# BaseBoard.net
KiCad netlist of a schematic drawn in EasyEDA Pro
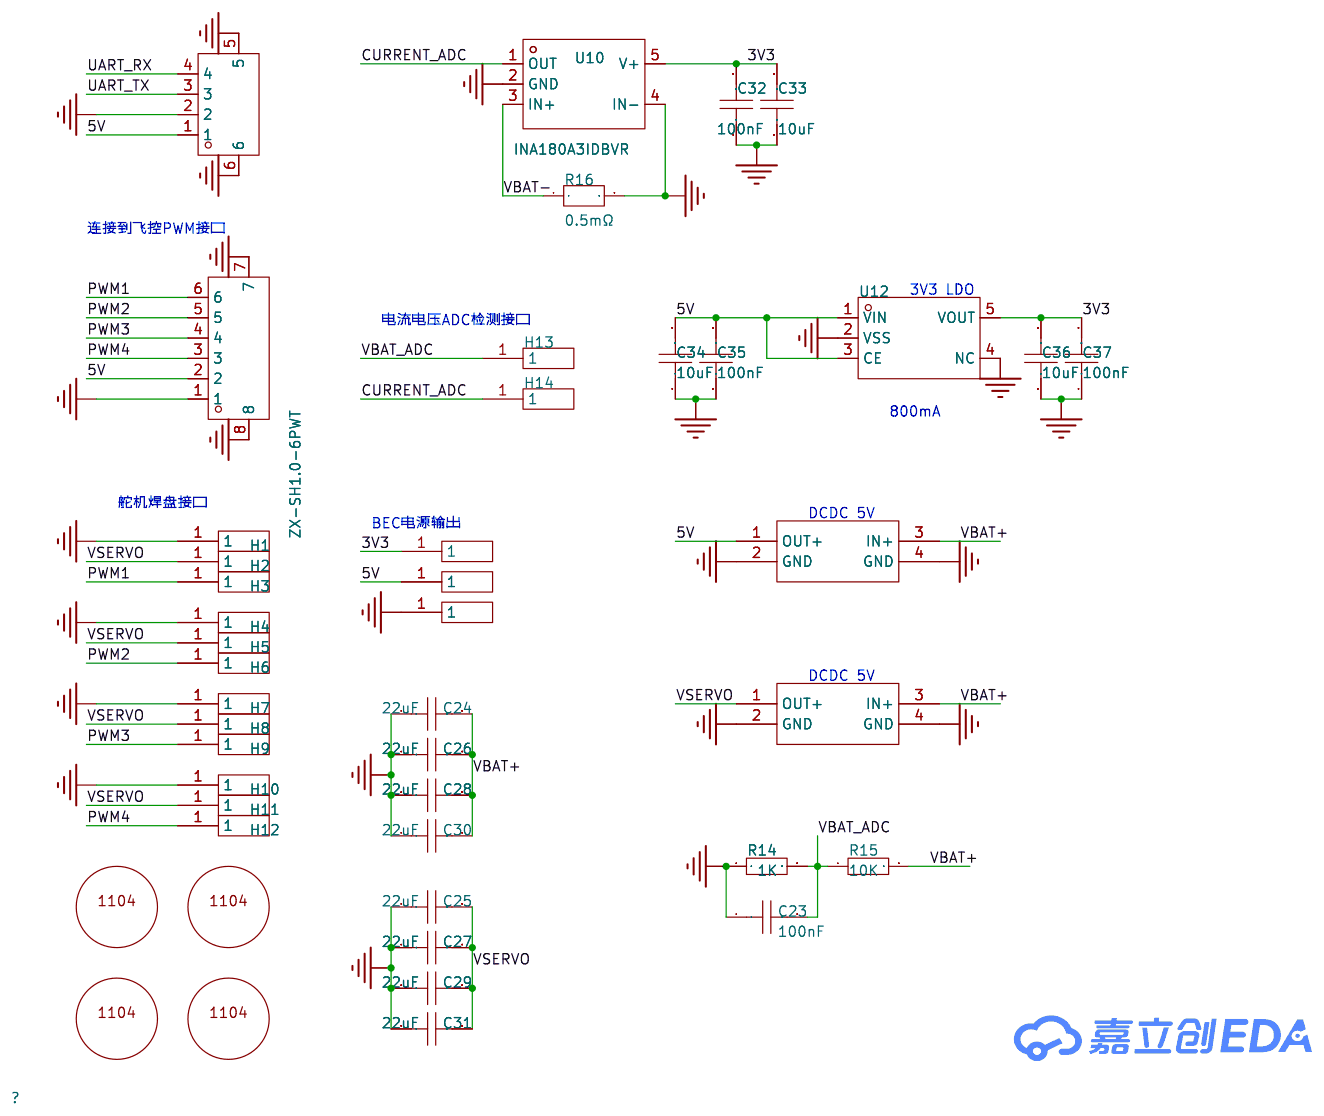
[diagram p0: schematic sheet]

(export (version "E")
  (design (tool "Eeschema 10.0.6"))
  (components
    (comp (ref "C23")
      (value "100nF")
      (footprint "easyedapro:C0805")
      (libsource (lib "easyedapro") (part "CapAcitance"))
    )
    (comp (ref "C24")
      (value "22uF")
      (footprint "easyedapro:C0805")
      (libsource (lib "easyedapro") (part "CapAcitance"))
    )
    (comp (ref "C25")
      (value "22uF")
      (footprint "easyedapro:C0805")
      (libsource (lib "easyedapro") (part "CapAcitance"))
    )
    (comp (ref "C26")
      (value "22uF")
      (footprint "easyedapro:C0805")
      (libsource (lib "easyedapro") (part "CapAcitance"))
    )
    (comp (ref "C27")
      (value "22uF")
      (footprint "easyedapro:C0805")
      (libsource (lib "easyedapro") (part "CapAcitance"))
    )
    (comp (ref "C28")
      (value "22uF")
      (footprint "easyedapro:C0805")
      (libsource (lib "easyedapro") (part "CapAcitance"))
    )
    (comp (ref "C29")
      (value "22uF")
      (footprint "easyedapro:C0805")
      (libsource (lib "easyedapro") (part "CapAcitance"))
    )
    (comp (ref "C30")
      (value "22uF")
      (footprint "easyedapro:C0805")
      (libsource (lib "easyedapro") (part "CapAcitance"))
    )
    (comp (ref "C31")
      (value "22uF")
      (footprint "easyedapro:C0805")
      (libsource (lib "easyedapro") (part "CapAcitance"))
    )
    (comp (ref "C32")
      (value "100nF")
      (footprint "easyedapro:C0805")
      (libsource (lib "easyedapro") (part "CapAcitance"))
    )
    (comp (ref "C33")
      (value "10uF")
      (footprint "easyedapro:C0805")
      (libsource (lib "easyedapro") (part "CapAcitance"))
    )
    (comp (ref "C34")
      (value "10uF")
      (footprint "easyedapro:C0805")
      (libsource (lib "easyedapro") (part "CapAcitance"))
    )
    (comp (ref "C35")
      (value "100nF")
      (footprint "easyedapro:C0805")
      (libsource (lib "easyedapro") (part "CapAcitance"))
    )
    (comp (ref "C36")
      (value "10uF")
      (footprint "easyedapro:C0805")
      (libsource (lib "easyedapro") (part "CapAcitance"))
    )
    (comp (ref "C37")
      (value "100nF")
      (footprint "easyedapro:C0805")
      (libsource (lib "easyedapro") (part "CapAcitance"))
    )
    (comp (ref "H1")
      (value "~")
      (footprint "easyedapro:飞控微型焊盘")
      (description "20250513 绘制接收机使用")
      (libsource (lib "easyedapro") (part "飞控微型焊盘"))
    )
    (comp (ref "H2")
      (value "~")
      (footprint "easyedapro:飞控微型焊盘")
      (description "20250513 绘制接收机使用")
      (libsource (lib "easyedapro") (part "飞控微型焊盘"))
    )
    (comp (ref "H3")
      (value "~")
      (footprint "easyedapro:飞控微型焊盘")
      (description "20250513 绘制接收机使用")
      (libsource (lib "easyedapro") (part "飞控微型焊盘"))
    )
    (comp (ref "H4")
      (value "~")
      (footprint "easyedapro:飞控微型焊盘")
      (description "20250513 绘制接收机使用")
      (libsource (lib "easyedapro") (part "飞控微型焊盘"))
    )
    (comp (ref "H5")
      (value "~")
      (footprint "easyedapro:飞控微型焊盘")
      (description "20250513 绘制接收机使用")
      (libsource (lib "easyedapro") (part "飞控微型焊盘"))
    )
    (comp (ref "H6")
      (value "~")
      (footprint "easyedapro:飞控微型焊盘")
      (description "20250513 绘制接收机使用")
      (libsource (lib "easyedapro") (part "飞控微型焊盘"))
    )
    (comp (ref "H7")
      (value "~")
      (footprint "easyedapro:飞控微型焊盘")
      (description "20250513 绘制接收机使用")
      (libsource (lib "easyedapro") (part "飞控微型焊盘"))
    )
    (comp (ref "H8")
      (value "~")
      (footprint "easyedapro:飞控微型焊盘")
      (description "20250513 绘制接收机使用")
      (libsource (lib "easyedapro") (part "飞控微型焊盘"))
    )
    (comp (ref "H9")
      (value "~")
      (footprint "easyedapro:飞控微型焊盘")
      (description "20250513 绘制接收机使用")
      (libsource (lib "easyedapro") (part "飞控微型焊盘"))
    )
    (comp (ref "H10")
      (value "~")
      (footprint "easyedapro:飞控微型焊盘")
      (description "20250513 绘制接收机使用")
      (libsource (lib "easyedapro") (part "飞控微型焊盘"))
    )
    (comp (ref "H11")
      (value "~")
      (footprint "easyedapro:飞控微型焊盘")
      (description "20250513 绘制接收机使用")
      (libsource (lib "easyedapro") (part "飞控微型焊盘"))
    )
    (comp (ref "H12")
      (value "~")
      (footprint "easyedapro:飞控微型焊盘")
      (description "20250513 绘制接收机使用")
      (libsource (lib "easyedapro") (part "飞控微型焊盘"))
    )
    (comp (ref "H13")
      (value "~")
      (footprint "easyedapro:飞控微型焊盘")
      (description "20250513 绘制接收机使用")
      (libsource (lib "easyedapro") (part "飞控微型焊盘"))
    )
    (comp (ref "H14")
      (value "~")
      (footprint "easyedapro:飞控微型焊盘")
      (description "20250513 绘制接收机使用")
      (libsource (lib "easyedapro") (part "飞控微型焊盘"))
    )
    (comp (ref "H15")
      (value "~")
      (footprint "easyedapro:飞控微型焊盘")
      (description "20250513 绘制接收机使用")
      (libsource (lib "easyedapro") (part "飞控微型焊盘"))
    )
    (comp (ref "H17")
      (value "~")
      (footprint "easyedapro:飞控微型焊盘")
      (description "20250513 绘制接收机使用")
      (libsource (lib "easyedapro") (part "飞控微型焊盘"))
    )
    (comp (ref "H18")
      (value "~")
      (footprint "easyedapro:飞控微型焊盘")
      (description "20250513 绘制接收机使用")
      (libsource (lib "easyedapro") (part "飞控微型焊盘"))
    )
    (comp (ref "R14") (value "1K") (footprint "easyedapro:R0603") (libsource (lib "easyedapro") (part "电阻")))
    (comp (ref "R15") (value "10K") (footprint "easyedapro:R0603") (libsource (lib "easyedapro") (part "电阻")))
    (comp (ref "R16")
      (value "0.5mΩ")
      (footprint "easyedapro:R2512")
      (description "电阻类型:采样电阻;阻值:0.5mΩ;精度:±1%;功率:3W;安装方式:贴片;")
      (fields
        (field (name "Manufacturer Part") "HoYLR2512E-3W-0.5mR-1%")
        (field (name "Manufacturer") "Milliohm(毫欧)")
      )
      (libsource (lib "easyedapro") (part "HOYLR2512E-3W-0.5MR-1%"))
    )
    (comp (ref "U4")
      (value "~")
      (footprint "easyedapro:1104无刷电机")
      (libsource (lib "easyedapro") (part "1104无刷电机"))
    )
    (comp (ref "U5")
      (value "~")
      (footprint "easyedapro:1104无刷电机")
      (libsource (lib "easyedapro") (part "1104无刷电机"))
    )
    (comp (ref "U6")
      (value "~")
      (footprint "easyedapro:1104无刷电机")
      (libsource (lib "easyedapro") (part "1104无刷电机"))
    )
    (comp (ref "U7")
      (value "~")
      (footprint "easyedapro:1104无刷电机")
      (libsource (lib "easyedapro") (part "1104无刷电机"))
    )
    (comp (ref "U8")
      (value "ZX-SH1.0-4PWT")
      (footprint "easyedapro:CONN-SMD_4P-P1.00_MEGASTAR_ZX-SH1.0-4PWT")
      (description "插针结构:1x4P;间距:1mm;安装方式:卧贴;参考系列:SH;总PIN数:4P;排数:1;每排PIN数:4;行距:-;额定电流:-;触头材质:黄铜;触头镀层:锡;工作温度范围:-;")
      (fields (field (name "Manufacturer") "Megastar(兆星)"))
      (libsource (lib "easyedapro") (part "ZX-SH1.0-4PWT"))
    )
    (comp (ref "U10")
      (value "INA180A3IDBVR")
      (footprint "easyedapro:SOT-23-5_L3.0-W1.7-P0.95-LS2.8-BR")
      (description "放大器数:单路;共模电压:-200mV~26V;增益:100V/V;带宽:150kHz;")
      (fields (field (name "Manufacturer") "TI(德州仪器)"))
      (libsource (lib "easyedapro") (part "INA180A3IDBVR"))
    )
    (comp (ref "U11")
      (value "ZX-SH1.0-6PWT")
      (footprint "easyedapro:CONN-SMD_6P-P1.00_MEGASTAR_ZX-SH1.0-6PWT")
      (description "插针结构:1x6P;间距:1mm;安装方式:卧贴;参考系列:SH;总PIN数:6P;排数:1;每排PIN数:6;行距:-;额定电流:-;触头材质:黄铜;触头镀层:锡;工作温度范围:-;")
      (fields (field (name "Manufacturer") "Megastar(兆星)"))
      (libsource (lib "easyedapro") (part "ZX-SH1.0-6PWT"))
    )
    (comp (ref "U12")
      (value "ME6217C33M5G")
      (footprint "easyedapro:SOT-23-5_L3.0-W1.7-P0.95-LS2.8-BR")
      (description "输出类型:固定;输出极性:正;最大输入电压:7V;输出电压:3.3V;输出电流:800mA;电源纹波抑制比(PSRR):65dB@(1kHz);")
      (fields (field (name "Manufacturer") "MICRONE(南京微盟)"))
      (libsource (lib "easyedapro") (part "ME6217C33M5G"))
    )
    (comp (ref "U13")
      (value "~")
      (footprint "easyedapro:迷你降压模块")
      (description "20250630 DCDC 5V")
      (libsource (lib "easyedapro") (part "迷你DCDC降压模块"))
    )
    (comp (ref "U14")
      (value "~")
      (footprint "easyedapro:迷你降压模块")
      (description "20250630 DCDC 5V")
      (libsource (lib "easyedapro") (part "迷你DCDC降压模块"))
    )
  )
  (nets
    (net (code "1") (name "/3V3") (class "Default")
      (node (ref "C32") (pin "2") (pinfunction "2_2") (pintype "input"))
      (node (ref "C33") (pin "2") (pinfunction "2_2") (pintype "input"))
      (node (ref "C36") (pin "2") (pinfunction "2_2") (pintype "input"))
      (node (ref "C37") (pin "2") (pinfunction "2_2") (pintype "input"))
      (node (ref "H15") (pin "1") (pinfunction "1_1") (pintype "input"))
      (node (ref "U10") (pin "5") (pinfunction "V+_5") (pintype "unspecified"))
      (node (ref "U12") (pin "5") (pinfunction "VOUT_5") (pintype "input"))
    )
    (net (code "2") (name "/5V") (class "Default")
      (node (ref "C34") (pin "2") (pinfunction "2_2") (pintype "input"))
      (node (ref "C35") (pin "2") (pinfunction "2_2") (pintype "input"))
      (node (ref "H17") (pin "1") (pinfunction "1_1") (pintype "input"))
      (node (ref "U11") (pin "2") (pinfunction "2_2") (pintype "unspecified"))
      (node (ref "U12") (pin "1") (pinfunction "VIN_1") (pintype "input"))
      (node (ref "U12") (pin "3") (pinfunction "CE_3") (pintype "input"))
      (node (ref "U13") (pin "1") (pinfunction "OUT+_1") (pintype "input"))
      (node (ref "U8") (pin "1") (pinfunction "1_1") (pintype "unspecified"))
    )
    (net (code "3") (name "/CURRENT_ADC") (class "Default")
      (node (ref "H14") (pin "1") (pinfunction "1_1") (pintype "input"))
      (node (ref "U10") (pin "1") (pinfunction "OUT_1") (pintype "unspecified"))
    )
    (net (code "4") (name "/PWM1") (class "Default")
      (node (ref "H3") (pin "1") (pinfunction "1_1") (pintype "input"))
      (node (ref "U11") (pin "6") (pinfunction "6_6") (pintype "unspecified"))
    )
    (net (code "5") (name "/PWM2") (class "Default")
      (node (ref "H6") (pin "1") (pinfunction "1_1") (pintype "input"))
      (node (ref "U11") (pin "5") (pinfunction "5_5") (pintype "unspecified"))
    )
    (net (code "6") (name "/PWM3") (class "Default")
      (node (ref "H9") (pin "1") (pinfunction "1_1") (pintype "input"))
      (node (ref "U11") (pin "4") (pinfunction "4_4") (pintype "unspecified"))
    )
    (net (code "7") (name "/PWM4") (class "Default")
      (node (ref "H12") (pin "1") (pinfunction "1_1") (pintype "input"))
      (node (ref "U11") (pin "3") (pinfunction "3_3") (pintype "unspecified"))
    )
    (net (code "8") (name "/UART_RX") (class "Default")
      (node (ref "U8") (pin "4") (pinfunction "4_4") (pintype "unspecified"))
    )
    (net (code "9") (name "/UART_TX") (class "Default")
      (node (ref "U8") (pin "3") (pinfunction "3_3") (pintype "unspecified"))
    )
    (net (code "10") (name "/VBAT+") (class "Default")
      (node (ref "C24") (pin "2") (pinfunction "2_2") (pintype "input"))
      (node (ref "C26") (pin "2") (pinfunction "2_2") (pintype "input"))
      (node (ref "C28") (pin "2") (pinfunction "2_2") (pintype "input"))
      (node (ref "C30") (pin "2") (pinfunction "2_2") (pintype "input"))
      (node (ref "R15") (pin "2") (pinfunction "2_2") (pintype "input"))
      (node (ref "U13") (pin "3") (pinfunction "IN+_3") (pintype "input"))
      (node (ref "U14") (pin "3") (pinfunction "IN+_3") (pintype "input"))
    )
    (net (code "11") (name "/VBAT-") (class "Default")
      (node (ref "R16") (pin "1") (pinfunction "1_1") (pintype "unspecified"))
      (node (ref "U10") (pin "3") (pinfunction "IN+_3") (pintype "unspecified"))
    )
    (net (code "12") (name "/VBAT_ADC") (class "Default")
      (node (ref "C23") (pin "2") (pinfunction "2_2") (pintype "input"))
      (node (ref "H13") (pin "1") (pinfunction "1_1") (pintype "input"))
      (node (ref "R14") (pin "2") (pinfunction "2_2") (pintype "input"))
      (node (ref "R15") (pin "1") (pinfunction "1_1") (pintype "input"))
    )
    (net (code "13") (name "/VSERVO") (class "Default")
      (node (ref "C25") (pin "2") (pinfunction "2_2") (pintype "input"))
      (node (ref "C27") (pin "2") (pinfunction "2_2") (pintype "input"))
      (node (ref "C29") (pin "2") (pinfunction "2_2") (pintype "input"))
      (node (ref "C31") (pin "2") (pinfunction "2_2") (pintype "input"))
      (node (ref "H11") (pin "1") (pinfunction "1_1") (pintype "input"))
      (node (ref "H2") (pin "1") (pinfunction "1_1") (pintype "input"))
      (node (ref "H5") (pin "1") (pinfunction "1_1") (pintype "input"))
      (node (ref "H8") (pin "1") (pinfunction "1_1") (pintype "input"))
      (node (ref "U14") (pin "1") (pinfunction "OUT+_1") (pintype "input"))
    )
    (net (code "14") (name "GND") (class "Default")
      (node (ref "C23") (pin "1") (pinfunction "1_1") (pintype "input"))
      (node (ref "C24") (pin "1") (pinfunction "1_1") (pintype "input"))
      (node (ref "C25") (pin "1") (pinfunction "1_1") (pintype "input"))
      (node (ref "C26") (pin "1") (pinfunction "1_1") (pintype "input"))
      (node (ref "C27") (pin "1") (pinfunction "1_1") (pintype "input"))
      (node (ref "C28") (pin "1") (pinfunction "1_1") (pintype "input"))
      (node (ref "C29") (pin "1") (pinfunction "1_1") (pintype "input"))
      (node (ref "C30") (pin "1") (pinfunction "1_1") (pintype "input"))
      (node (ref "C31") (pin "1") (pinfunction "1_1") (pintype "input"))
      (node (ref "C32") (pin "1") (pinfunction "1_1") (pintype "input"))
      (node (ref "C33") (pin "1") (pinfunction "1_1") (pintype "input"))
      (node (ref "C34") (pin "1") (pinfunction "1_1") (pintype "input"))
      (node (ref "C35") (pin "1") (pinfunction "1_1") (pintype "input"))
      (node (ref "C36") (pin "1") (pinfunction "1_1") (pintype "input"))
      (node (ref "C37") (pin "1") (pinfunction "1_1") (pintype "input"))
      (node (ref "H1") (pin "1") (pinfunction "1_1") (pintype "input"))
      (node (ref "H10") (pin "1") (pinfunction "1_1") (pintype "input"))
      (node (ref "H18") (pin "1") (pinfunction "1_1") (pintype "input"))
      (node (ref "H4") (pin "1") (pinfunction "1_1") (pintype "input"))
      (node (ref "H7") (pin "1") (pinfunction "1_1") (pintype "input"))
      (node (ref "R14") (pin "1") (pinfunction "1_1") (pintype "input"))
      (node (ref "R16") (pin "2") (pinfunction "2_2") (pintype "unspecified"))
      (node (ref "U10") (pin "2") (pinfunction "GND_2") (pintype "unspecified"))
      (node (ref "U10") (pin "4") (pinfunction "IN-_4") (pintype "unspecified"))
      (node (ref "U11") (pin "1") (pinfunction "1_1") (pintype "unspecified"))
      (node (ref "U11") (pin "7") (pinfunction "7_7") (pintype "unspecified"))
      (node (ref "U11") (pin "8") (pinfunction "8_8") (pintype "unspecified"))
      (node (ref "U12") (pin "2") (pinfunction "VSS_2") (pintype "input"))
      (node (ref "U12") (pin "4") (pinfunction "NC_4") (pintype "input"))
      (node (ref "U13") (pin "2") (pinfunction "GND_2") (pintype "input"))
      (node (ref "U13") (pin "4") (pinfunction "GND_4") (pintype "input"))
      (node (ref "U14") (pin "2") (pinfunction "GND_2") (pintype "input"))
      (node (ref "U14") (pin "4") (pinfunction "GND_4") (pintype "input"))
      (node (ref "U8") (pin "2") (pinfunction "2_2") (pintype "unspecified"))
      (node (ref "U8") (pin "5") (pinfunction "5_5") (pintype "unspecified"))
      (node (ref "U8") (pin "6") (pinfunction "6_6") (pintype "unspecified"))
    )
  )
)
